# Radio.net
KiCad netlist of a schematic drawn in Altium Designer
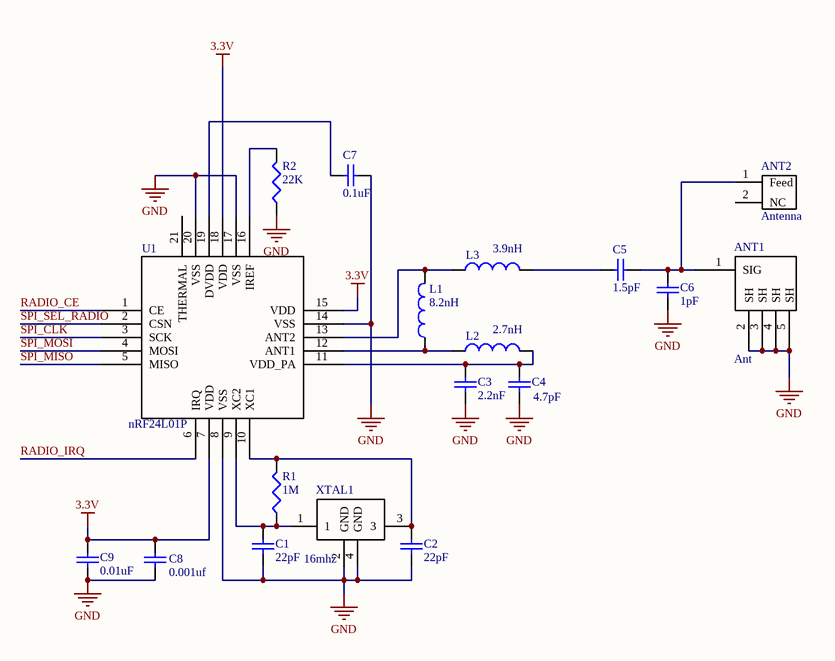
[diagram p0: Radio.SchDoc]

(export (version "E")
  (design (tool "Eeschema 10.0.6"))
  (components
    (comp (ref "ANT1") (value "Ant") (footprint "AntennaSMA") (libsource (lib "mrone") (part "AntennaConn")))
    (comp (ref "ANT2") (value "Antenna") (footprint "antenna") (libsource (lib "mrone") (part "Antenna")))
    (comp (ref "C1")
      (value "22pF")
      (footprint "CAPC1005L")
      (description "Capacitor (Semiconductor SIM Model)")
      (fields (field (name "Comment") "Cap Semi") (field (name "PUBLISHER") "Altium Limited"))
      (libsource (lib "Miscellaneous Devices") (part "Cap Semi"))
    )
    (comp (ref "C2")
      (value "22pF")
      (footprint "CAPC1005L")
      (description "Capacitor (Semiconductor SIM Model)")
      (fields (field (name "Comment") "Cap Semi") (field (name "PUBLISHER") "Altium Limited"))
      (libsource (lib "Miscellaneous Devices") (part "Cap Semi"))
    )
    (comp (ref "C3")
      (value "2.2nF")
      (footprint "CAPC1005L")
      (description "Capacitor (Semiconductor SIM Model)")
      (fields (field (name "Comment") "Cap Semi") (field (name "PUBLISHER") "Altium Limited"))
      (libsource (lib "Miscellaneous Devices") (part "Cap Semi"))
    )
    (comp (ref "C4")
      (value "4.7pF")
      (footprint "CAPC1005L")
      (description "Capacitor (Semiconductor SIM Model)")
      (fields (field (name "Comment") "Cap Semi") (field (name "PUBLISHER") "Altium Limited"))
      (libsource (lib "Miscellaneous Devices") (part "Cap Semi"))
    )
    (comp (ref "C5")
      (value "1.5pF")
      (footprint "CAPC1005L")
      (description "Capacitor (Semiconductor SIM Model)")
      (fields (field (name "Comment") "Cap Semi") (field (name "PUBLISHER") "Altium Limited"))
      (libsource (lib "Miscellaneous Devices") (part "Cap Semi"))
    )
    (comp (ref "C6")
      (value "1pF")
      (footprint "CAPC1005L")
      (description "Capacitor (Semiconductor SIM Model)")
      (fields (field (name "Comment") "Cap Semi") (field (name "PUBLISHER") "Altium Limited"))
      (libsource (lib "Miscellaneous Devices") (part "Cap Semi"))
    )
    (comp (ref "C7")
      (value "0.1uF")
      (footprint "CAPC1005L")
      (description "Capacitor (Semiconductor SIM Model)")
      (fields (field (name "Comment") "Cap Semi") (field (name "PUBLISHER") "Altium Limited"))
      (libsource (lib "Miscellaneous Devices") (part "Cap Semi"))
    )
    (comp (ref "C8")
      (value "0.001uf")
      (footprint "CAPC1005L")
      (description "Capacitor (Semiconductor SIM Model)")
      (fields (field (name "Comment") "Cap Semi") (field (name "PUBLISHER") "Altium Limited"))
      (libsource (lib "Miscellaneous Devices") (part "Cap Semi"))
    )
    (comp (ref "C9")
      (value "0.01uF")
      (footprint "CAPC1005L")
      (description "Capacitor (Semiconductor SIM Model)")
      (fields (field (name "Comment") "Cap Semi") (field (name "PUBLISHER") "Altium Limited"))
      (libsource (lib "Miscellaneous Devices") (part "Cap Semi"))
    )
    (comp (ref "L1")
      (value "8.2nH")
      (footprint "INDC1005AL")
      (description "Inductor")
      (fields (field (name "PUBLISHER") "Altium Limited"))
      (libsource (lib "Miscellaneous Devices") (part "Inductor"))
    )
    (comp (ref "L2")
      (value "2.7nH")
      (footprint "INDC1005AL")
      (description "Inductor")
      (fields (field (name "PUBLISHER") "Altium Limited"))
      (libsource (lib "Miscellaneous Devices") (part "Inductor"))
    )
    (comp (ref "L3")
      (value "3.9nH")
      (footprint "INDC1005AL")
      (description "Inductor")
      (fields (field (name "PUBLISHER") "Altium Limited"))
      (libsource (lib "Miscellaneous Devices") (part "Inductor"))
    )
    (comp (ref "R1")
      (value "1M")
      (footprint "RESC1608L")
      (description "Resistor")
      (fields (field (name "Comment") "Res3") (field (name "PUBLISHER") "Altium Limited"))
      (libsource (lib "Miscellaneous Devices") (part "Res3"))
    )
    (comp (ref "R2")
      (value "22K")
      (footprint "RESC1608L")
      (description "Resistor")
      (fields (field (name "Comment") "Res3") (field (name "PUBLISHER") "Altium Limited"))
      (libsource (lib "Miscellaneous Devices") (part "Res3"))
    )
    (comp (ref "U1")
      (value "nRF24L01P")
      (footprint "QFN-20")
      (libsource (lib "mrone") (part "radio-nRF24L01P"))
    )
    (comp (ref "XTAL1")
      (value "16mhz")
      (footprint "RadioCrystal")
      (fields (field (name "Comment") "RADIO CRYSTAL"))
      (libsource (lib "Schematic Components") (part "RadioCrystal"))
    )
  )
  (nets
    (net (code "1") (name "/RADIO_CE") (class "Default")
      (node (ref "U1") (pin "1") (pinfunction "CE_1") (pintype "passive"))
    )
    (net (code "2") (name "/RADIO_IRQ") (class "Default")
      (node (ref "U1") (pin "6") (pinfunction "IRQ_6") (pintype "passive"))
    )
    (net (code "3") (name "/SPI_CLK") (class "Default")
      (node (ref "U1") (pin "3") (pinfunction "SCK_3") (pintype "passive"))
    )
    (net (code "4") (name "/SPI_MISO") (class "Default")
      (node (ref "U1") (pin "5") (pinfunction "MISO_5") (pintype "passive"))
    )
    (net (code "5") (name "/SPI_MOSI") (class "Default")
      (node (ref "U1") (pin "4") (pinfunction "MOSI_4") (pintype "passive"))
    )
    (net (code "6") (name "/SPI_SEL_RADIO") (class "Default")
      (node (ref "U1") (pin "2") (pinfunction "CSN_2") (pintype "passive"))
    )
    (net (code "7") (name "3.3V") (class "Default")
      (node (ref "C8") (pin "2") (pinfunction "2_2") (pintype "passive"))
      (node (ref "C9") (pin "2") (pinfunction "2_2") (pintype "passive"))
      (node (ref "U1") (pin "15") (pinfunction "VDD_15") (pintype "passive"))
      (node (ref "U1") (pin "18") (pinfunction "VDD_18") (pintype "passive"))
      (node (ref "U1") (pin "7") (pinfunction "VDD_7") (pintype "passive"))
    )
    (net (code "8") (name "GND") (class "Default")
      (node (ref "ANT1") (pin "2") (pinfunction "SH_2") (pintype "passive"))
      (node (ref "ANT1") (pin "3") (pinfunction "SH_3") (pintype "passive"))
      (node (ref "ANT1") (pin "4") (pinfunction "SH_4") (pintype "passive"))
      (node (ref "ANT1") (pin "5") (pinfunction "SH_5") (pintype "passive"))
      (node (ref "C1") (pin "1") (pinfunction "1_1") (pintype "passive"))
      (node (ref "C2") (pin "1") (pinfunction "1_1") (pintype "passive"))
      (node (ref "C3") (pin "1") (pinfunction "1_1") (pintype "passive"))
      (node (ref "C4") (pin "1") (pinfunction "1_1") (pintype "passive"))
      (node (ref "C6") (pin "1") (pinfunction "1_1") (pintype "passive"))
      (node (ref "C7") (pin "1") (pinfunction "1_1") (pintype "passive"))
      (node (ref "C8") (pin "1") (pinfunction "1_1") (pintype "passive"))
      (node (ref "C9") (pin "1") (pinfunction "1_1") (pintype "passive"))
      (node (ref "R2") (pin "1") (pinfunction "1_1") (pintype "passive"))
      (node (ref "U1") (pin "14") (pinfunction "VSS_14") (pintype "passive"))
      (node (ref "U1") (pin "17") (pinfunction "VSS_17") (pintype "passive"))
      (node (ref "U1") (pin "20") (pinfunction "VSS_20") (pintype "passive"))
      (node (ref "U1") (pin "8") (pinfunction "VSS_8") (pintype "passive"))
      (node (ref "XTAL1") (pin "2") (pinfunction "GND_2") (pintype "passive"))
      (node (ref "XTAL1") (pin "4") (pinfunction "GND_4") (pintype "passive"))
    )
    (net (code "9") (name "Net-(ANT1-SIG)") (class "Default")
      (node (ref "ANT1") (pin "1") (pinfunction "SIG_1") (pintype "passive"))
      (node (ref "ANT2") (pin "1") (pinfunction "Feed_1") (pintype "passive"))
      (node (ref "C5") (pin "1") (pinfunction "1_1") (pintype "passive"))
      (node (ref "C6") (pin "2") (pinfunction "2_2") (pintype "passive"))
    )
    (net (code "10") (name "Net-(C5-Pad2)") (class "Default")
      (node (ref "C5") (pin "2") (pinfunction "2_2") (pintype "passive"))
      (node (ref "L3") (pin "2") (pinfunction "2_2") (pintype "passive"))
    )
    (net (code "11") (name "Net-(U1-ANT1)") (class "Default")
      (node (ref "L1") (pin "1") (pinfunction "1_1") (pintype "passive"))
      (node (ref "L2") (pin "1") (pinfunction "1_1") (pintype "passive"))
      (node (ref "U1") (pin "12") (pinfunction "ANT1_12") (pintype "passive"))
    )
    (net (code "12") (name "Net-(U1-ANT2)") (class "Default")
      (node (ref "L1") (pin "2") (pinfunction "2_2") (pintype "passive"))
      (node (ref "L3") (pin "1") (pinfunction "1_1") (pintype "passive"))
      (node (ref "U1") (pin "13") (pinfunction "ANT2_13") (pintype "passive"))
    )
    (net (code "13") (name "Net-(U1-DVDD)") (class "Default")
      (node (ref "C7") (pin "2") (pinfunction "2_2") (pintype "passive"))
      (node (ref "U1") (pin "19") (pinfunction "DVDD_19") (pintype "passive"))
    )
    (net (code "14") (name "Net-(U1-IREF)") (class "Default")
      (node (ref "R2") (pin "2") (pinfunction "2_2") (pintype "passive"))
      (node (ref "U1") (pin "16") (pinfunction "IREF_16") (pintype "passive"))
    )
    (net (code "15") (name "Net-(U1-VDD_PA)") (class "Default")
      (node (ref "C3") (pin "2") (pinfunction "2_2") (pintype "passive"))
      (node (ref "C4") (pin "2") (pinfunction "2_2") (pintype "passive"))
      (node (ref "L2") (pin "2") (pinfunction "2_2") (pintype "passive"))
      (node (ref "U1") (pin "11") (pinfunction "VDD_PA_11") (pintype "passive"))
    )
    (net (code "16") (name "Net-(U1-XC1)") (class "Default")
      (node (ref "C2") (pin "2") (pinfunction "2_2") (pintype "passive"))
      (node (ref "R1") (pin "2") (pinfunction "2_2") (pintype "passive"))
      (node (ref "U1") (pin "10") (pinfunction "XC1_10") (pintype "passive"))
      (node (ref "XTAL1") (pin "3") (pinfunction "3_3") (pintype "passive"))
    )
    (net (code "17") (name "Net-(U1-XC2)") (class "Default")
      (node (ref "C1") (pin "2") (pinfunction "2_2") (pintype "passive"))
      (node (ref "R1") (pin "1") (pinfunction "1_1") (pintype "passive"))
      (node (ref "U1") (pin "9") (pinfunction "XC2_9") (pintype "passive"))
      (node (ref "XTAL1") (pin "1") (pinfunction "1_1") (pintype "passive"))
    )
    (net (code "18") (name "unconnected-(ANT2-NC-Pad2)") (class "Default")
      (node (ref "ANT2") (pin "2") (pinfunction "NC_2") (pintype "passive"))
    )
    (net (code "19") (name "unconnected-(U1-THERMAL-Pad21)") (class "Default")
      (node (ref "U1") (pin "21") (pinfunction "THERMAL_21") (pintype "passive"))
    )
  )
)
